# Schematic.net
KiCad netlist of a schematic drawn in Altium Designer
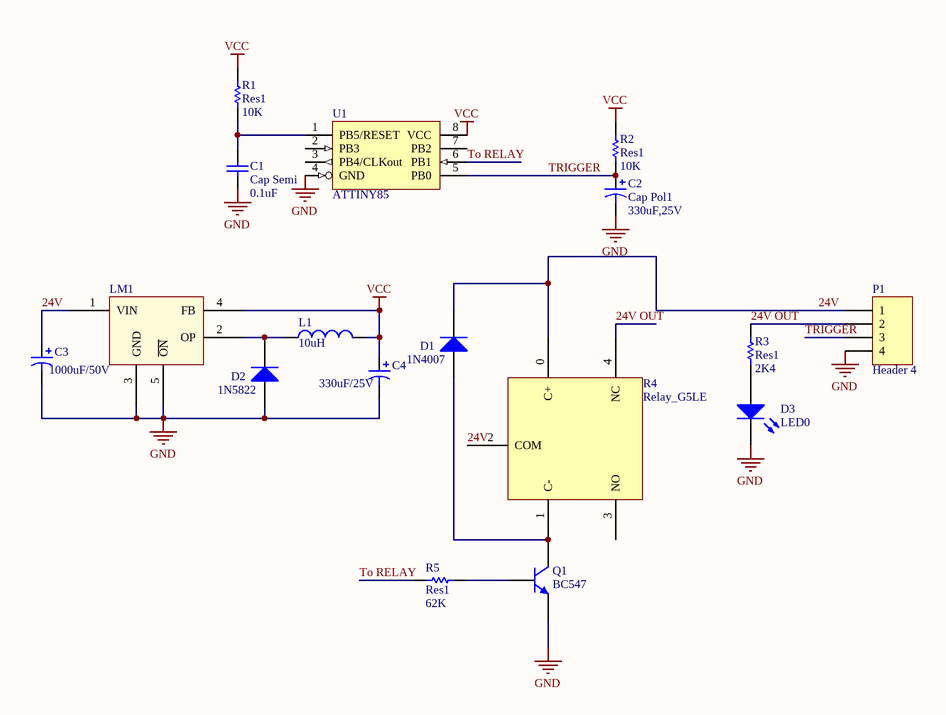
[diagram p0: Schematic.SchDoc]

(export (version "E")
  (design (tool "Eeschema 10.0.6"))
  (components
    (comp (ref "C1")
      (value "Cap Semi")
      (footprint "C1206")
      (description "Capacitor (Semiconductor SIM Model)")
      (fields (field (name "ALTIUM_VALUE") "0.1uF") (field (name "PUBLISHER") "Altium Limited"))
      (libsource (lib "Miscellaneous Devices") (part "Cap Semi"))
    )
    (comp (ref "C2")
      (value "Cap Pol1")
      (footprint "Polar Cap 9 mm")
      (description "Polarized Capacitor (Radial)")
      (fields (field (name "ALTIUM_VALUE") "330uF,25V") (field (name "PUBLISHER") "Altium Limited"))
      (libsource (lib "Miscellaneous Devices") (part "Cap Pol1"))
    )
    (comp (ref "C3")
      (value "1000uF/50V")
      (footprint "polar Cap")
      (description "Polarized Capacitor (Radial)")
      (fields (field (name "Comment") "Cap Pol1") (field (name "PUBLISHER") "Altium Limited"))
      (libsource (lib "Miscellaneous Devices") (part "Cap Pol1"))
    )
    (comp (ref "C4")
      (value "330uF/25V")
      (footprint "12mm")
      (description "Polarized Capacitor (Radial)")
      (fields (field (name "Comment") "Cap Pol1") (field (name "PUBLISHER") "Altium Limited"))
      (libsource (lib "Miscellaneous Devices") (part "Cap Pol1"))
    )
    (comp (ref "D1")
      (value "1N4007")
      (footprint "AXIAL-0.4")
      (description "3 Amp Medium Power Silicon Rectifier Diode")
      (fields (field (name "PUBLISHER") "Altium Limited"))
      (libsource (lib "Miscellaneous Devices") (part "Diode 1N5408"))
    )
    (comp (ref "D2")
      (value "1N5822")
      (footprint "AXIAL-0.6")
      (description "3 Amp Medium Power Silicon Rectifier Diode")
      (fields (field (name "PUBLISHER") "Altium Limited"))
      (libsource (lib "Miscellaneous Devices") (part "Diode 1N5408"))
    )
    (comp (ref "D3")
      (value "LED0")
      (footprint "LED")
      (description "Typical INFRARED GaAs LED")
      (fields (field (name "PUBLISHER") "Altium Limited"))
      (libsource (lib "Miscellaneous Devices") (part "LED0"))
    )
    (comp (ref "L1")
      (value "10uH")
      (footprint "WireWound")
      (description "Inductor")
      (fields (field (name "PUBLISHER") "Altium Limited"))
      (libsource (lib "Miscellaneous Devices") (part "Inductor"))
    )
    (comp (ref "LM1")
      (value "LM2576")
      (footprint "LM2576")
      (description "Switcher")
      (libsource (lib "LM2576") (part "Component_1"))
    )
    (comp (ref "P1")
      (value "Header 4")
      (footprint "HDR1X4")
      (description "Header, 4-Pin")
      (fields (field (name "PUBLISHER") "Altium Limited"))
      (libsource (lib "Miscellaneous Connectors") (part "Header 4"))
    )
    (comp (ref "Q1")
      (value "BC547")
      (footprint "TO-92")
      (description "NPN General Purpose Amplifier")
      (fields (field (name "PUBLISHER") "Altium Limited"))
      (libsource (lib "Miscellaneous Devices") (part "2N3904"))
    )
    (comp (ref "R1")
      (value "Res1")
      (footprint "1206")
      (description "Resistor")
      (fields (field (name "ALTIUM_VALUE") "10K") (field (name "PUBLISHER") "Altium Limited"))
      (libsource (lib "Miscellaneous Devices") (part "Res1"))
    )
    (comp (ref "R2")
      (value "Res1")
      (footprint "1206")
      (description "Resistor")
      (fields (field (name "ALTIUM_VALUE") "10K") (field (name "PUBLISHER") "Altium Limited"))
      (libsource (lib "Miscellaneous Devices") (part "Res1"))
    )
    (comp (ref "R3")
      (value "Res1")
      (footprint "1206")
      (description "Resistor")
      (fields (field (name "ALTIUM_VALUE") "2K4") (field (name "PUBLISHER") "Altium Limited"))
      (libsource (lib "Miscellaneous Devices") (part "Res1"))
    )
    (comp (ref "R4")
      (value "Relay_G5LE")
      (footprint "G5LE_relay")
      (libsource (lib "G5LE_relay") (part "Relay_G5LE"))
    )
    (comp (ref "R5")
      (value "Res1")
      (footprint "1206")
      (description "Resistor")
      (fields (field (name "ALTIUM_VALUE") "62K") (field (name "PUBLISHER") "Altium Limited"))
      (libsource (lib "Miscellaneous Devices") (part "Res1"))
    )
    (comp (ref "U1")
      (value "ATTINY85")
      (footprint "DIP8")
      (description "Precision Timer")
      (fields (field (name "PUBLISHER") "Altium Limited"))
      (libsource (lib "ATTINY85") (part "NE555D"))
    )
  )
  (nets
    (net (code "1") (name "/24V") (class "Default")
      (node (ref "C3") (pin "1") (pinfunction "1_1") (pintype "passive"))
      (node (ref "D1") (pin "2") (pinfunction "K_2") (pintype "passive"))
      (node (ref "LM1") (pin "1") (pinfunction "VIN_1") (pintype "passive"))
      (node (ref "P1") (pin "1") (pinfunction "1_1") (pintype "passive"))
      (node (ref "R4") (pin "0") (pinfunction "C+_0") (pintype "passive"))
      (node (ref "R4") (pin "2") (pinfunction "COM_2") (pintype "passive"))
    )
    (net (code "2") (name "/24V OUT") (class "Default")
      (node (ref "P1") (pin "2") (pinfunction "2_2") (pintype "passive"))
      (node (ref "R3") (pin "2") (pinfunction "2_2") (pintype "passive"))
      (node (ref "R4") (pin "4") (pinfunction "NC_4") (pintype "passive"))
    )
    (net (code "3") (name "/TRIGGER") (class "Default")
      (node (ref "C2") (pin "1") (pinfunction "1_1") (pintype "passive"))
      (node (ref "P1") (pin "3") (pinfunction "3_3") (pintype "passive"))
      (node (ref "R2") (pin "1") (pinfunction "1_1") (pintype "passive"))
      (node (ref "U1") (pin "5") (pinfunction "PB0_5") (pintype "passive"))
    )
    (net (code "4") (name "/To RELAY") (class "Default")
      (node (ref "R5") (pin "2") (pinfunction "2_2") (pintype "passive"))
      (node (ref "U1") (pin "6") (pinfunction "PB1_6") (pintype "input"))
    )
    (net (code "5") (name "GND") (class "Default")
      (node (ref "C1") (pin "1") (pinfunction "1_1") (pintype "passive"))
      (node (ref "C2") (pin "2") (pinfunction "2_2") (pintype "passive"))
      (node (ref "C3") (pin "2") (pinfunction "2_2") (pintype "passive"))
      (node (ref "C4") (pin "2") (pinfunction "2_2") (pintype "passive"))
      (node (ref "D2") (pin "1") (pinfunction "A_1") (pintype "passive"))
      (node (ref "D3") (pin "2") (pinfunction "K_2") (pintype "passive"))
      (node (ref "LM1") (pin "3") (pinfunction "GND_3") (pintype "passive"))
      (node (ref "LM1") (pin "5") (pinfunction "~{ON}_5") (pintype "passive"))
      (node (ref "P1") (pin "4") (pinfunction "4_4") (pintype "passive"))
      (node (ref "Q1") (pin "1") (pinfunction "E_1") (pintype "passive"))
      (node (ref "U1") (pin "4") (pinfunction "GND_4") (pintype "input"))
    )
    (net (code "6") (name "Net-(D1-A)") (class "Default")
      (node (ref "D1") (pin "1") (pinfunction "A_1") (pintype "passive"))
      (node (ref "Q1") (pin "3") (pinfunction "C_3") (pintype "passive"))
      (node (ref "R4") (pin "1") (pinfunction "C-_1") (pintype "passive"))
    )
    (net (code "7") (name "Net-(D2-K)") (class "Default")
      (node (ref "D2") (pin "2") (pinfunction "K_2") (pintype "passive"))
      (node (ref "L1") (pin "1") (pinfunction "1_1") (pintype "passive"))
      (node (ref "LM1") (pin "2") (pinfunction "OP_2") (pintype "passive"))
    )
    (net (code "8") (name "Net-(D3-A)") (class "Default")
      (node (ref "D3") (pin "1") (pinfunction "A_1") (pintype "passive"))
      (node (ref "R3") (pin "1") (pinfunction "1_1") (pintype "passive"))
    )
    (net (code "9") (name "Net-(Q1-B)") (class "Default")
      (node (ref "Q1") (pin "2") (pinfunction "B_2") (pintype "passive"))
      (node (ref "R5") (pin "1") (pinfunction "1_1") (pintype "passive"))
    )
    (net (code "10") (name "Net-(U1-PB5{slash}RESET)") (class "Default")
      (node (ref "C1") (pin "2") (pinfunction "2_2") (pintype "passive"))
      (node (ref "R1") (pin "1") (pinfunction "1_1") (pintype "passive"))
      (node (ref "U1") (pin "1") (pinfunction "PB5/RESET_1") (pintype "power_in"))
    )
    (net (code "11") (name "VCC") (class "Default")
      (node (ref "C4") (pin "1") (pinfunction "1_1") (pintype "passive"))
      (node (ref "L1") (pin "2") (pinfunction "2_2") (pintype "passive"))
      (node (ref "LM1") (pin "4") (pinfunction "FB_4") (pintype "passive"))
      (node (ref "R1") (pin "2") (pinfunction "2_2") (pintype "passive"))
      (node (ref "R2") (pin "2") (pinfunction "2_2") (pintype "passive"))
      (node (ref "U1") (pin "8") (pinfunction "VCC_8") (pintype "power_in"))
    )
    (net (code "12") (name "unconnected-(R4-NO-Pad3)") (class "Default")
      (node (ref "R4") (pin "3") (pinfunction "NO_3") (pintype "passive"))
    )
    (net (code "13") (name "unconnected-(U1-PB2-Pad7)") (class "Default")
      (node (ref "U1") (pin "7") (pinfunction "PB2_7") (pintype "open_collector"))
    )
    (net (code "14") (name "unconnected-(U1-PB3-Pad2)") (class "Default")
      (node (ref "U1") (pin "2") (pinfunction "PB3_2") (pintype "input"))
    )
    (net (code "15") (name "unconnected-(U1-PB4{slash}CLKout-Pad3)") (class "Default")
      (node (ref "U1") (pin "3") (pinfunction "PB4/CLKout_3") (pintype "output"))
    )
  )
)
